# OnOnfre_dual_mola_ssr_rev3_4.net
KiCad netlist of a schematic drawn in EAGLE
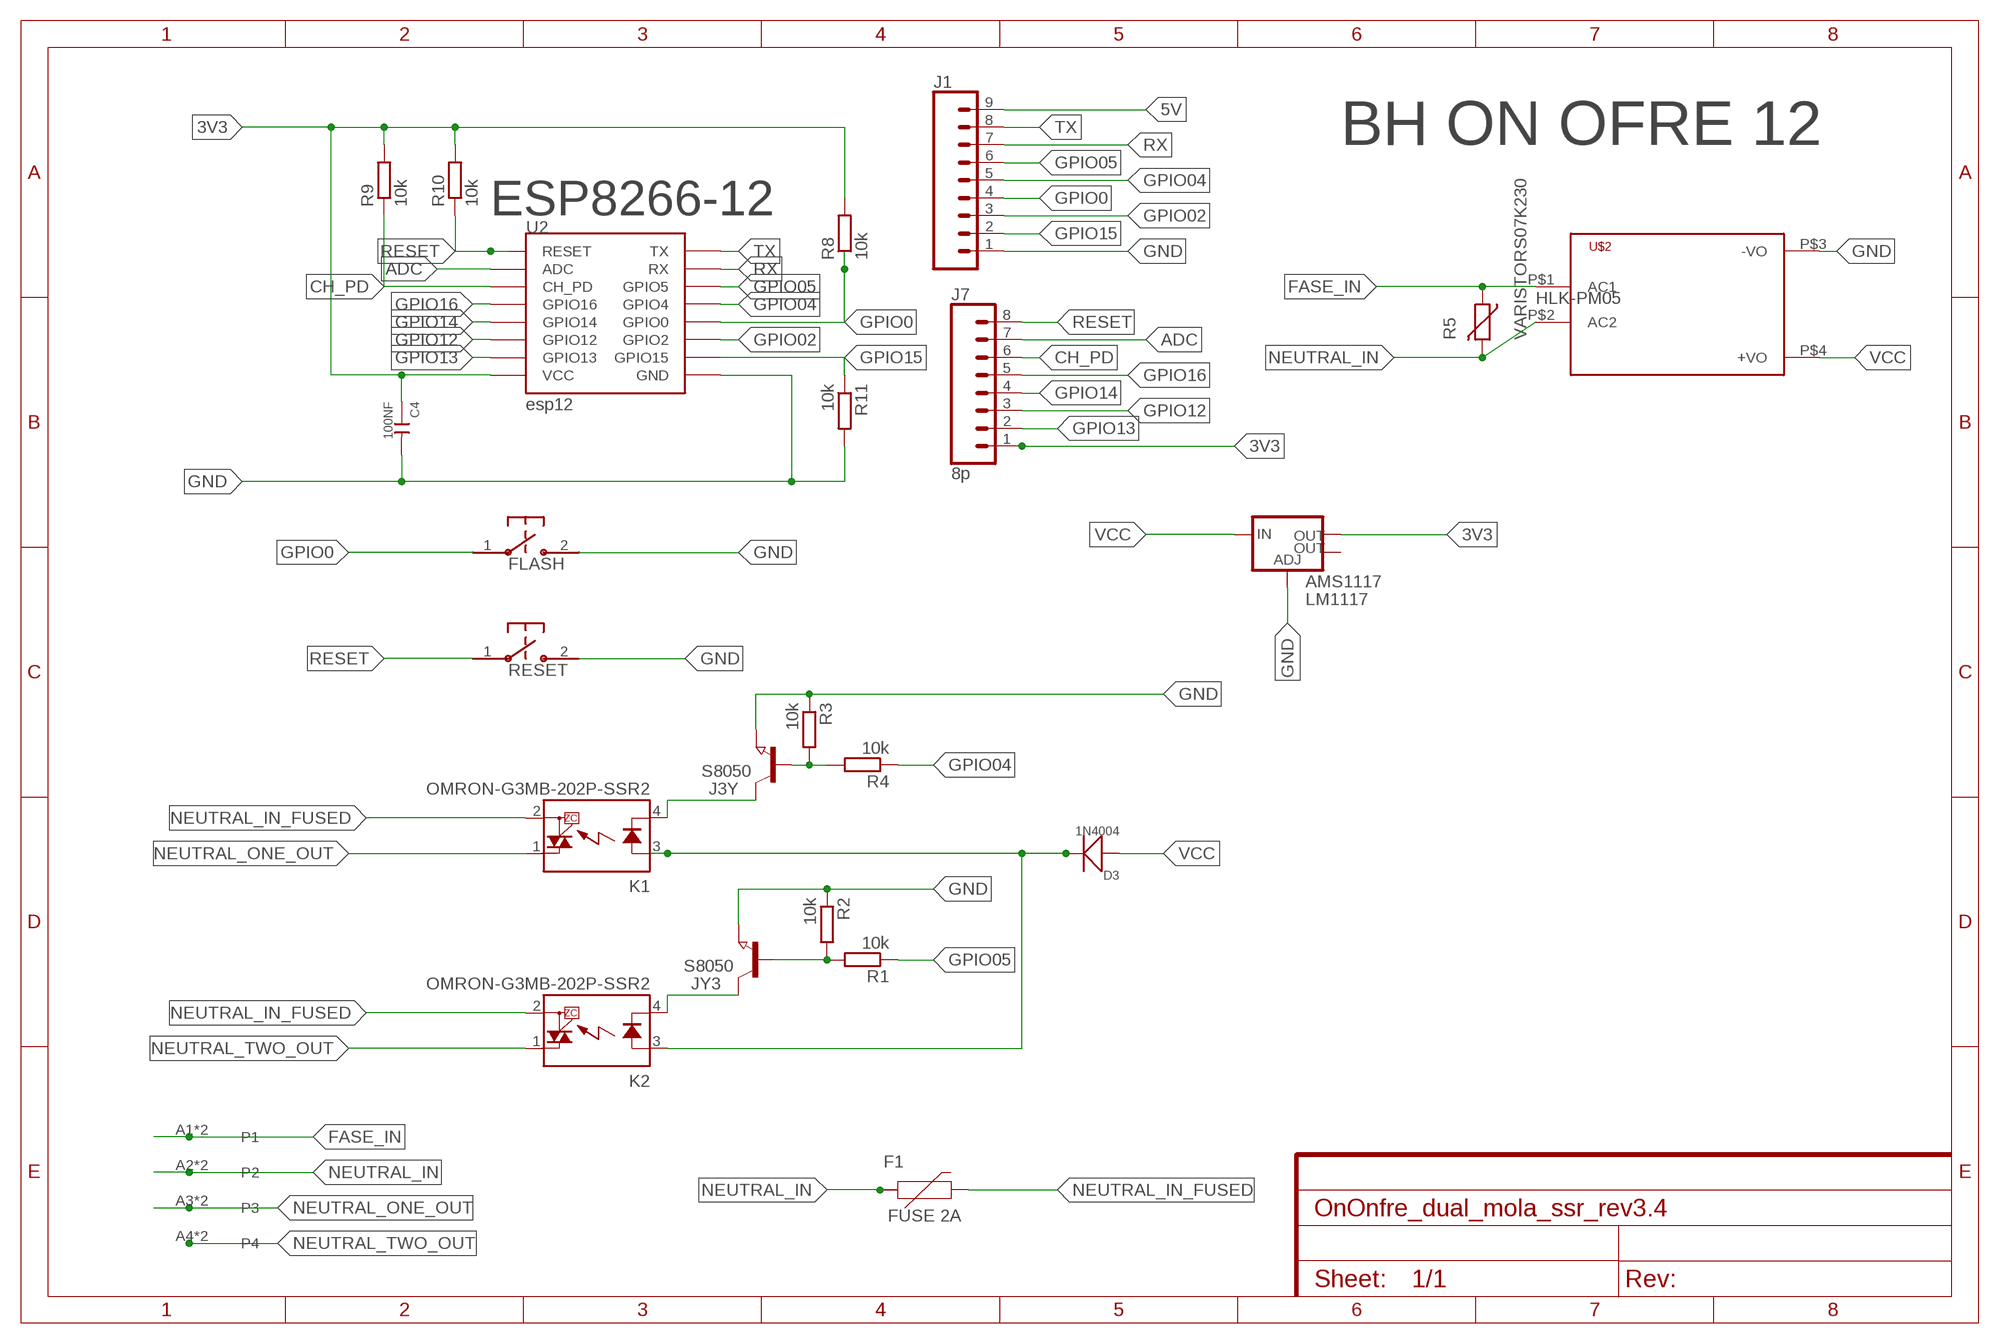
[diagram p0: schematic, sheet 1]

(export (version "E")
  (design (tool "Eeschema 10.0.6"))
  (components
    (comp (ref "AMS1117")
      (value "LM1117")
      (footprint "eagle-import:SOT223")
      (libsource (lib "eagle-import") (part "V_REG_LM1117SOT223"))
    )
    (comp (ref "C4")
      (value "100NF")
      (footprint "eagle-import:C1206")
      (fields (field (name "MPN") "CC1206KKX7RCBB102"))
      (libsource (lib "eagle-import") (part "CERAMIC-1NF-1KV-10%-X7R?(1206)"))
    )
    (comp (ref "D3")
      (value "1N4004")
      (footprint "eagle-import:DO-214AC")
      (fields (field (name "MPN") "1N4007"))
      (libsource (lib "eagle-import") (part "DIODE-GEN-PURPOSE-1KV-1A(DO-214AC)"))
    )
    (comp (ref "F1")
      (value "FUSE 2A")
      (footprint "eagle-import:PTH")
      (libsource (lib "eagle-import") (part "PPTC_PTH"))
    )
    (comp (ref "FLASH")
      (value "B3U-1000P-2P-SMD")
      (footprint "eagle-import:B3U-1000P")
      (fields (field (name "MANUFACTURER") "Omron") (field (name "MPN") "B3U-1000P"))
      (libsource (lib "eagle-import") (part "B3U-1000P"))
    )
    (comp (ref "J1")
      (value "CONN_09")
      (footprint "eagle-import:1X09")
      (libsource (lib "eagle-import") (part "CONN_09"))
    )
    (comp (ref "J3Y")
      (value "S8050")
      (footprint "eagle-import:SOT23")
      (libsource (lib "eagle-import") (part "NPN-TRANSISTOR_SOT23"))
    )
    (comp (ref "J7")
      (value "8p")
      (footprint "eagle-import:1X08")
      (libsource (lib "eagle-import") (part "CONN_08{dblquote}"))
    )
    (comp (ref "JY3")
      (value "S8050")
      (footprint "eagle-import:SOT23")
      (libsource (lib "eagle-import") (part "NPN-TRANSISTOR_SOT23"))
    )
    (comp (ref "K1")
      (value "OMRON-G3MB-202P-SSR2")
      (footprint "eagle-import:OMRON-G3MB-202P-SSR")
      (fields (field (name "MPN") "S202S02F"))
      (libsource (lib "eagle-import") (part "OMRON-G3MB-202P-SSR2"))
    )
    (comp (ref "K2")
      (value "OMRON-G3MB-202P-SSR2")
      (footprint "eagle-import:OMRON-G3MB-202P-SSR")
      (fields (field (name "MPN") "S202S02F"))
      (libsource (lib "eagle-import") (part "OMRON-G3MB-202P-SSR2"))
    )
    (comp (ref "R1")
      (value "10k")
      (footprint "eagle-import:R0603")
      (libsource (lib "eagle-import") (part "R-EU_R0603"))
    )
    (comp (ref "R2")
      (value "10k")
      (footprint "eagle-import:R0603")
      (libsource (lib "eagle-import") (part "R-EU_R0603"))
    )
    (comp (ref "R3")
      (value "10k")
      (footprint "eagle-import:R0603")
      (libsource (lib "eagle-import") (part "R-EU_R0603"))
    )
    (comp (ref "R4")
      (value "10k")
      (footprint "eagle-import:R0603")
      (libsource (lib "eagle-import") (part "R-EU_R0603"))
    )
    (comp (ref "R5")
      (value "VARISTORS07K230")
      (footprint "eagle-import:S07K230")
      (libsource (lib "eagle-import") (part "VARISTORS07K230"))
    )
    (comp (ref "R8")
      (value "10k")
      (footprint "eagle-import:R0603")
      (libsource (lib "eagle-import") (part "R-EU_R0603"))
    )
    (comp (ref "R9")
      (value "10k")
      (footprint "eagle-import:R0603")
      (libsource (lib "eagle-import") (part "R-EU_R0603"))
    )
    (comp (ref "R10")
      (value "10k")
      (footprint "eagle-import:R0603")
      (libsource (lib "eagle-import") (part "R-EU_R0603"))
    )
    (comp (ref "R11")
      (value "10k")
      (footprint "eagle-import:R0603")
      (libsource (lib "eagle-import") (part "R-EU_R0603"))
    )
    (comp (ref "RESET")
      (value "B3U-1000P-2P-SMD")
      (footprint "eagle-import:B3U-1000P")
      (fields (field (name "MANUFACTURER") "Omron") (field (name "MPN") "B3U-1000P"))
      (libsource (lib "eagle-import") (part "B3U-1000P"))
    )
    (comp (ref "U$1")
      (value "4P4P")
      (footprint "eagle-import:4P")
      (libsource (lib "eagle-import") (part "4P4P"))
    )
    (comp (ref "U$2")
      (value "HKLPM01")
      (footprint "eagle-import:HKLPM01")
      (libsource (lib "eagle-import") (part "HKLPM01"))
    )
    (comp (ref "U2")
      (value "esp12")
      (footprint "eagle-import:ESP12-SMD")
      (libsource (lib "eagle-import") (part "ESP12SMD"))
    )
  )
  (nets
    (net (code "1") (name "3V3") (class "Default")
      (node (ref "AMS1117") (pin "2") (pinfunction "OUT_2") (pintype "output"))
      (node (ref "C4") (pin "1") (pinfunction "1_1") (pintype "passive"))
      (node (ref "J7") (pin "1") (pinfunction "1_1") (pintype "passive"))
      (node (ref "R10") (pin "2") (pinfunction "2_2") (pintype "passive"))
      (node (ref "R8") (pin "2") (pinfunction "2_2") (pintype "passive"))
      (node (ref "R9") (pin "2") (pinfunction "2_2") (pintype "passive"))
      (node (ref "U2") (pin "VCC") (pinfunction "VCC_VCC") (pintype "bidirectional"))
    )
    (net (code "2") (name "5V") (class "Default")
      (node (ref "D3") (pin "2") (pinfunction "-_2") (pintype "passive"))
      (node (ref "J1") (pin "9") (pinfunction "9_9") (pintype "passive"))
      (node (ref "K1") (pin "3") (pinfunction "A_3") (pintype "passive"))
      (node (ref "K2") (pin "3") (pinfunction "A_3") (pintype "passive"))
    )
    (net (code "3") (name "ADC") (class "Default")
      (node (ref "J7") (pin "7") (pinfunction "7_7") (pintype "passive"))
      (node (ref "U2") (pin "ADC") (pinfunction "ADC_ADC") (pintype "bidirectional"))
    )
    (net (code "4") (name "CH_PD") (class "Default")
      (node (ref "J7") (pin "6") (pinfunction "6_6") (pintype "passive"))
      (node (ref "R9") (pin "1") (pinfunction "1_1") (pintype "passive"))
      (node (ref "U2") (pin "CH_PD") (pinfunction "CH_PD_CH_PD") (pintype "bidirectional"))
    )
    (net (code "5") (name "FASE_IN") (class "Default")
      (node (ref "R5") (pin "1") (pinfunction "1_1") (pintype "passive"))
      (node (ref "U$1") (pin "A1") (pinfunction "P1_A1") (pintype "bidirectional"))
      (node (ref "U$1") (pin "B1") (pinfunction "P1_B1") (pintype "bidirectional"))
      (node (ref "U$2") (pin "P$1") (pinfunction "AC1_P$1") (pintype "bidirectional"))
    )
    (net (code "6") (name "GND") (class "Default")
      (node (ref "AMS1117") (pin "1") (pinfunction "ADJ_1") (pintype "input"))
      (node (ref "C4") (pin "2") (pinfunction "2_2") (pintype "passive"))
      (node (ref "FLASH") (pin "2") (pinfunction "P$2_2") (pintype "passive"))
      (node (ref "J1") (pin "1") (pinfunction "1_1") (pintype "passive"))
      (node (ref "J3Y") (pin "2") (pinfunction "E_2") (pintype "passive"))
      (node (ref "JY3") (pin "2") (pinfunction "E_2") (pintype "passive"))
      (node (ref "R11") (pin "2") (pinfunction "2_2") (pintype "passive"))
      (node (ref "R2") (pin "1") (pinfunction "1_1") (pintype "passive"))
      (node (ref "R3") (pin "1") (pinfunction "1_1") (pintype "passive"))
      (node (ref "RESET") (pin "2") (pinfunction "P$2_2") (pintype "passive"))
      (node (ref "U$2") (pin "P$3") (pinfunction "-VO_P$3") (pintype "bidirectional"))
      (node (ref "U2") (pin "GND") (pinfunction "GND_GND") (pintype "bidirectional"))
    )
    (net (code "7") (name "GPIO0") (class "Default")
      (node (ref "FLASH") (pin "1") (pinfunction "P$1_1") (pintype "passive"))
      (node (ref "J1") (pin "4") (pinfunction "4_4") (pintype "passive"))
      (node (ref "R8") (pin "1") (pinfunction "1_1") (pintype "passive"))
      (node (ref "U2") (pin "GPIO0") (pinfunction "GPIO0_GPIO0") (pintype "bidirectional"))
    )
    (net (code "8") (name "GPIO02") (class "Default")
      (node (ref "J1") (pin "3") (pinfunction "3_3") (pintype "passive"))
      (node (ref "U2") (pin "GPIO2") (pinfunction "GPIO2_GPIO2") (pintype "bidirectional"))
    )
    (net (code "9") (name "GPIO04") (class "Default")
      (node (ref "J1") (pin "5") (pinfunction "5_5") (pintype "passive"))
      (node (ref "R4") (pin "1") (pinfunction "1_1") (pintype "passive"))
      (node (ref "U2") (pin "GPIO4") (pinfunction "GPIO4_GPIO4") (pintype "bidirectional"))
    )
    (net (code "10") (name "GPIO05") (class "Default")
      (node (ref "J1") (pin "6") (pinfunction "6_6") (pintype "passive"))
      (node (ref "R1") (pin "1") (pinfunction "1_1") (pintype "passive"))
      (node (ref "U2") (pin "GPIO5") (pinfunction "GPIO5_GPIO5") (pintype "bidirectional"))
    )
    (net (code "11") (name "GPIO12") (class "Default")
      (node (ref "J7") (pin "3") (pinfunction "3_3") (pintype "passive"))
      (node (ref "U2") (pin "GPIO12") (pinfunction "GPIO12_GPIO12") (pintype "bidirectional"))
    )
    (net (code "12") (name "GPIO13") (class "Default")
      (node (ref "J7") (pin "2") (pinfunction "2_2") (pintype "passive"))
      (node (ref "U2") (pin "GPIO13") (pinfunction "GPIO13_GPIO13") (pintype "bidirectional"))
    )
    (net (code "13") (name "GPIO14") (class "Default")
      (node (ref "J7") (pin "4") (pinfunction "4_4") (pintype "passive"))
      (node (ref "U2") (pin "GPIO14") (pinfunction "GPIO14_GPIO14") (pintype "bidirectional"))
    )
    (net (code "14") (name "GPIO15") (class "Default")
      (node (ref "J1") (pin "2") (pinfunction "2_2") (pintype "passive"))
      (node (ref "R11") (pin "1") (pinfunction "1_1") (pintype "passive"))
      (node (ref "U2") (pin "GPIO15") (pinfunction "GPIO15_GPIO15") (pintype "bidirectional"))
    )
    (net (code "15") (name "GPIO16") (class "Default")
      (node (ref "J7") (pin "5") (pinfunction "5_5") (pintype "passive"))
      (node (ref "U2") (pin "GPIO16") (pinfunction "GPIO16_GPIO16") (pintype "bidirectional"))
    )
    (net (code "16") (name "NEUTRAL_IN") (class "Default")
      (node (ref "F1") (pin "P$1") (pinfunction "1_P$1") (pintype "bidirectional"))
      (node (ref "R5") (pin "2") (pinfunction "2_2") (pintype "passive"))
      (node (ref "U$1") (pin "A2") (pinfunction "P2_A2") (pintype "bidirectional"))
      (node (ref "U$1") (pin "B2") (pinfunction "P2_B2") (pintype "bidirectional"))
      (node (ref "U$2") (pin "P$2") (pinfunction "AC2_P$2") (pintype "bidirectional"))
    )
    (net (code "17") (name "NEUTRAL_IN_FUSED") (class "Default")
      (node (ref "F1") (pin "P$2") (pinfunction "2_P$2") (pintype "bidirectional"))
      (node (ref "K1") (pin "2") (pinfunction "DS2_2") (pintype "passive"))
      (node (ref "K2") (pin "2") (pinfunction "DS2_2") (pintype "passive"))
    )
    (net (code "18") (name "NEUTRAL_ONE_OUT") (class "Default")
      (node (ref "K1") (pin "1") (pinfunction "DS1_1") (pintype "passive"))
      (node (ref "U$1") (pin "A3") (pinfunction "P3_A3") (pintype "bidirectional"))
      (node (ref "U$1") (pin "B3") (pinfunction "P3_B3") (pintype "bidirectional"))
    )
    (net (code "19") (name "NEUTRAL_TWO_OUT") (class "Default")
      (node (ref "K2") (pin "1") (pinfunction "DS1_1") (pintype "passive"))
      (node (ref "U$1") (pin "A4") (pinfunction "P4_A4") (pintype "bidirectional"))
      (node (ref "U$1") (pin "B4") (pinfunction "P4_B4") (pintype "bidirectional"))
    )
    (net (code "20") (name "Net-(J3Y-B)") (class "Default")
      (node (ref "J3Y") (pin "1") (pinfunction "B_1") (pintype "passive"))
      (node (ref "R3") (pin "2") (pinfunction "2_2") (pintype "passive"))
      (node (ref "R4") (pin "2") (pinfunction "2_2") (pintype "passive"))
    )
    (net (code "21") (name "Net-(J3Y-C)") (class "Default")
      (node (ref "J3Y") (pin "3") (pinfunction "C_3") (pintype "passive"))
      (node (ref "K1") (pin "4") (pinfunction "K_4") (pintype "passive"))
    )
    (net (code "22") (name "Net-(JY3-B)") (class "Default")
      (node (ref "JY3") (pin "1") (pinfunction "B_1") (pintype "passive"))
      (node (ref "R1") (pin "2") (pinfunction "2_2") (pintype "passive"))
      (node (ref "R2") (pin "2") (pinfunction "2_2") (pintype "passive"))
    )
    (net (code "23") (name "Net-(JY3-C)") (class "Default")
      (node (ref "JY3") (pin "3") (pinfunction "C_3") (pintype "passive"))
      (node (ref "K2") (pin "4") (pinfunction "K_4") (pintype "passive"))
    )
    (net (code "24") (name "RESET") (class "Default")
      (node (ref "J7") (pin "8") (pinfunction "8_8") (pintype "passive"))
      (node (ref "R10") (pin "1") (pinfunction "1_1") (pintype "passive"))
      (node (ref "RESET") (pin "1") (pinfunction "P$1_1") (pintype "passive"))
      (node (ref "U2") (pin "RESET") (pinfunction "RESET_RESET") (pintype "bidirectional"))
    )
    (net (code "25") (name "RX") (class "Default")
      (node (ref "J1") (pin "7") (pinfunction "7_7") (pintype "passive"))
      (node (ref "U2") (pin "RXD0") (pinfunction "RX_RXD0") (pintype "bidirectional"))
    )
    (net (code "26") (name "TX") (class "Default")
      (node (ref "J1") (pin "8") (pinfunction "8_8") (pintype "passive"))
      (node (ref "U2") (pin "TXD0") (pinfunction "TX_TXD0") (pintype "bidirectional"))
    )
    (net (code "27") (name "VCC") (class "Default")
      (node (ref "AMS1117") (pin "3") (pinfunction "IN_3") (pintype "input"))
      (node (ref "D3") (pin "1") (pinfunction "+_1") (pintype "passive"))
      (node (ref "U$2") (pin "P$4") (pinfunction "+VO_P$4") (pintype "bidirectional"))
    )
    (net (code "28") (name "unconnected-(AMS1117-OUT-Pad4)") (class "Default")
      (node (ref "AMS1117") (pin "4") (pinfunction "OUT_4") (pintype "output"))
    )
  )
)
